# PCB-ACM.net
KiCad netlist of a schematic drawn in EAGLE
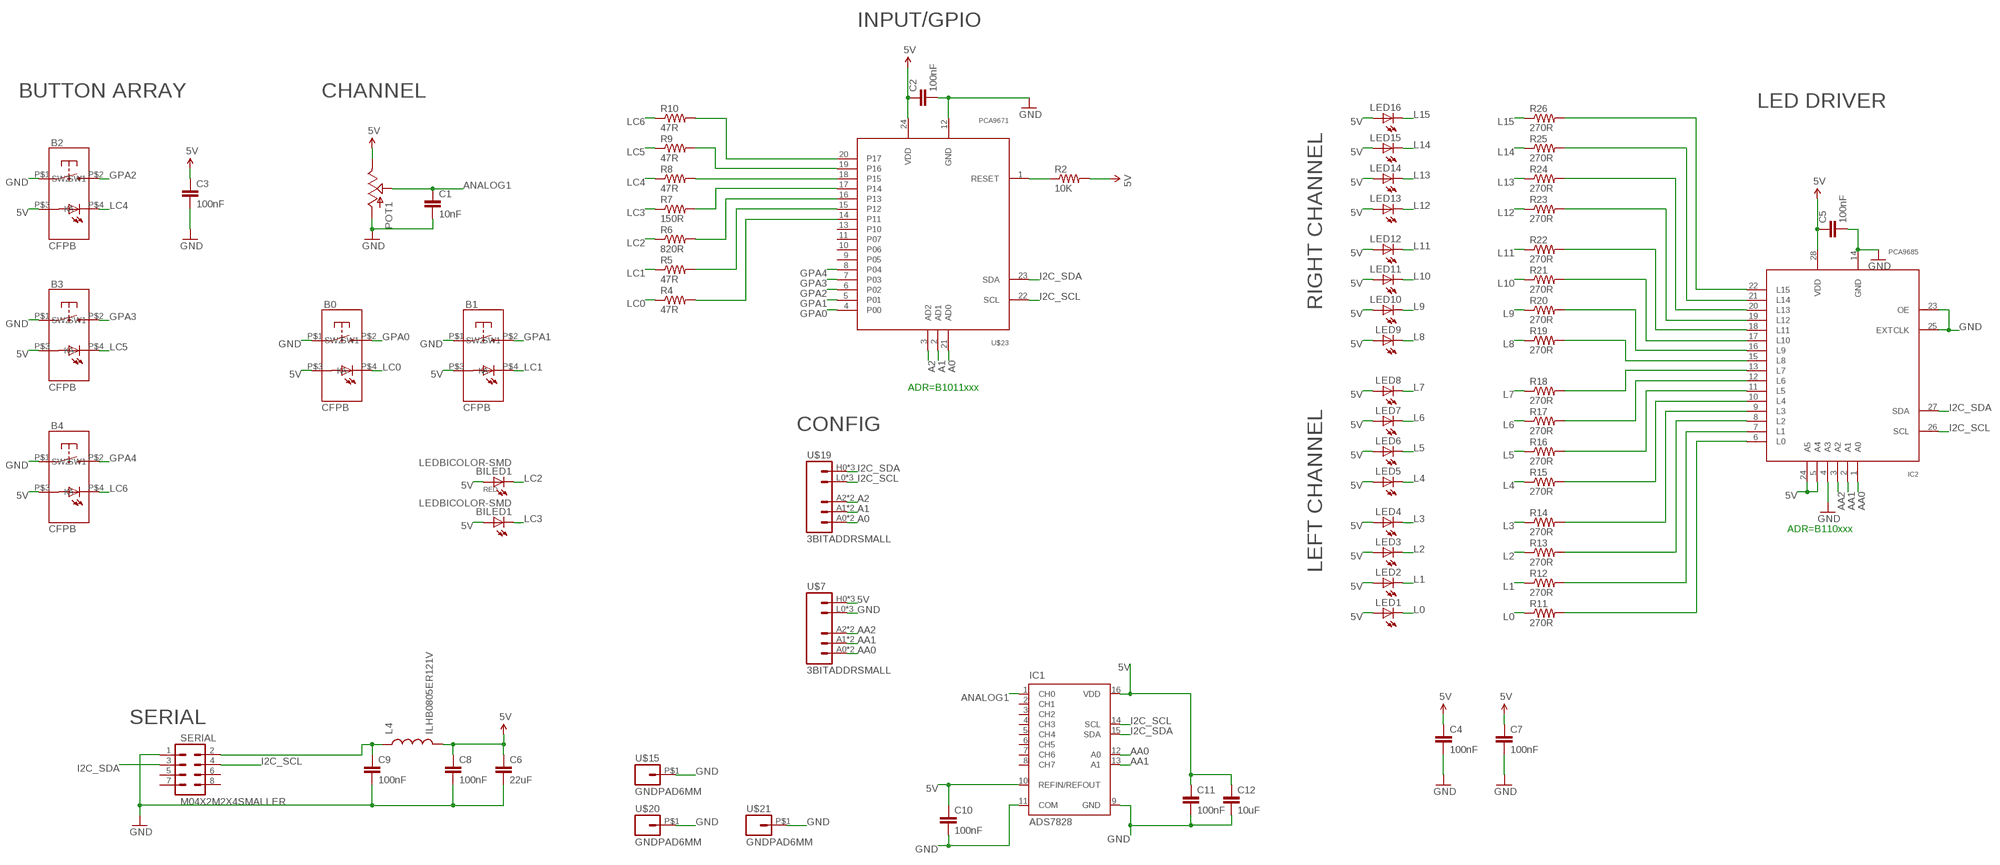
[diagram p0: schematic, sheet 1]

(export (version "E")
  (design (tool "Eeschema 10.0.6"))
  (components
    (comp (ref "B0")
      (value "CFPB")
      (footprint "eagle-import:CFPB-6_9MM")
      (libsource (lib "eagle-import") (part "CFPB"))
    )
    (comp (ref "B1")
      (value "CFPB")
      (footprint "eagle-import:CFPB-6_9MM")
      (libsource (lib "eagle-import") (part "CFPB"))
    )
    (comp (ref "B2")
      (value "CFPB")
      (footprint "eagle-import:CFPB-6_9MM")
      (libsource (lib "eagle-import") (part "CFPB"))
    )
    (comp (ref "B3")
      (value "CFPB")
      (footprint "eagle-import:CFPB-6_9MM")
      (libsource (lib "eagle-import") (part "CFPB"))
    )
    (comp (ref "B4")
      (value "CFPB")
      (footprint "eagle-import:CFPB-6_9MM")
      (libsource (lib "eagle-import") (part "CFPB"))
    )
    (comp (ref "BILED1")
      (value "LEDBICOLOR-SMD")
      (footprint "eagle-import:LEDBICOLOR-SMD")
      (libsource (lib "eagle-import") (part "LEDBICOLOR-SMD"))
    )
    (comp (ref "C1")
      (value "10nF")
      (footprint "eagle-import:0603-CAP")
      (libsource (lib "eagle-import") (part "CAP0603-CAP"))
    )
    (comp (ref "C2")
      (value "100nF")
      (footprint "eagle-import:0603-CAP")
      (libsource (lib "eagle-import") (part "CAP0603-CAP"))
    )
    (comp (ref "C3")
      (value "100nF")
      (footprint "eagle-import:0603-CAP")
      (libsource (lib "eagle-import") (part "CAP0603-CAP"))
    )
    (comp (ref "C4")
      (value "100nF")
      (footprint "eagle-import:0603-CAP")
      (libsource (lib "eagle-import") (part "CAP0603-CAP"))
    )
    (comp (ref "C5")
      (value "100nF")
      (footprint "eagle-import:0603-CAP")
      (libsource (lib "eagle-import") (part "CAP0603-CAP"))
    )
    (comp (ref "C6")
      (value "22uF")
      (footprint "eagle-import:0805")
      (libsource (lib "eagle-import") (part "CAP0805"))
    )
    (comp (ref "C7")
      (value "100nF")
      (footprint "eagle-import:0603-CAP")
      (libsource (lib "eagle-import") (part "CAP0603-CAP"))
    )
    (comp (ref "C8")
      (value "100nF")
      (footprint "eagle-import:0603-CAP")
      (libsource (lib "eagle-import") (part "CAP0603-CAP"))
    )
    (comp (ref "C9")
      (value "100nF")
      (footprint "eagle-import:0603-CAP")
      (libsource (lib "eagle-import") (part "CAP0603-CAP"))
    )
    (comp (ref "C10")
      (value "100nF")
      (footprint "eagle-import:0603-CAP")
      (libsource (lib "eagle-import") (part "CAP0603-CAP"))
    )
    (comp (ref "C11")
      (value "100nF")
      (footprint "eagle-import:0603-CAP")
      (libsource (lib "eagle-import") (part "CAP0603-CAP"))
    )
    (comp (ref "C12")
      (value "10uF")
      (footprint "eagle-import:0805")
      (libsource (lib "eagle-import") (part "CAP0805"))
    )
    (comp (ref "IC1")
      (value "ADS7828")
      (footprint "eagle-import:TSSOP16-PW")
      (fields (field (name "MF") "TEXAS INSTRUMENTS") (field (name "MPN") "ADS7828E/250"))
      (libsource (lib "eagle-import") (part "ADS7828"))
    )
    (comp (ref "IC2")
      (value "PCA9685")
      (footprint "eagle-import:TSSOP28")
      (libsource (lib "eagle-import") (part "PCA9685"))
    )
    (comp (ref "L4")
      (value "ILHB0805ER121V")
      (footprint "eagle-import:0805")
      (libsource (lib "eagle-import") (part "INDUCTOR0805"))
    )
    (comp (ref "LED1")
      (value "LED3MM")
      (footprint "eagle-import:LED3MM")
      (libsource (lib "eagle-import") (part "LED3MM"))
    )
    (comp (ref "LED2")
      (value "LED3MM")
      (footprint "eagle-import:LED3MM")
      (libsource (lib "eagle-import") (part "LED3MM"))
    )
    (comp (ref "LED3")
      (value "LED3MM")
      (footprint "eagle-import:LED3MM")
      (libsource (lib "eagle-import") (part "LED3MM"))
    )
    (comp (ref "LED4")
      (value "LED3MM")
      (footprint "eagle-import:LED3MM")
      (libsource (lib "eagle-import") (part "LED3MM"))
    )
    (comp (ref "LED5")
      (value "LED3MM")
      (footprint "eagle-import:LED3MM")
      (libsource (lib "eagle-import") (part "LED3MM"))
    )
    (comp (ref "LED6")
      (value "LED3MM")
      (footprint "eagle-import:LED3MM")
      (libsource (lib "eagle-import") (part "LED3MM"))
    )
    (comp (ref "LED7")
      (value "LED3MM")
      (footprint "eagle-import:LED3MM")
      (libsource (lib "eagle-import") (part "LED3MM"))
    )
    (comp (ref "LED8")
      (value "LED3MM")
      (footprint "eagle-import:LED3MM")
      (libsource (lib "eagle-import") (part "LED3MM"))
    )
    (comp (ref "LED9")
      (value "LED3MM")
      (footprint "eagle-import:LED3MM")
      (libsource (lib "eagle-import") (part "LED3MM"))
    )
    (comp (ref "LED10")
      (value "LED3MM")
      (footprint "eagle-import:LED3MM")
      (libsource (lib "eagle-import") (part "LED3MM"))
    )
    (comp (ref "LED11")
      (value "LED3MM")
      (footprint "eagle-import:LED3MM")
      (libsource (lib "eagle-import") (part "LED3MM"))
    )
    (comp (ref "LED12")
      (value "LED3MM")
      (footprint "eagle-import:LED3MM")
      (libsource (lib "eagle-import") (part "LED3MM"))
    )
    (comp (ref "LED13")
      (value "LED3MM")
      (footprint "eagle-import:LED3MM")
      (libsource (lib "eagle-import") (part "LED3MM"))
    )
    (comp (ref "LED14")
      (value "LED3MM")
      (footprint "eagle-import:LED3MM")
      (libsource (lib "eagle-import") (part "LED3MM"))
    )
    (comp (ref "LED15")
      (value "LED3MM")
      (footprint "eagle-import:LED3MM")
      (libsource (lib "eagle-import") (part "LED3MM"))
    )
    (comp (ref "LED16")
      (value "LED3MM")
      (footprint "eagle-import:LED3MM")
      (libsource (lib "eagle-import") (part "LED3MM"))
    )
    (comp (ref "POT1")
      (value "POT")
      (footprint "eagle-import:ALPS_POT")
      (libsource (lib "eagle-import") (part "POT"))
    )
    (comp (ref "R2")
      (value "10K")
      (footprint "eagle-import:0603-RES")
      (libsource (lib "eagle-import") (part "RESISTOR0603-RES"))
    )
    (comp (ref "R4")
      (value "47R")
      (footprint "eagle-import:0603-RES")
      (libsource (lib "eagle-import") (part "RESISTOR0603-RES"))
    )
    (comp (ref "R5")
      (value "47R")
      (footprint "eagle-import:0603-RES")
      (libsource (lib "eagle-import") (part "RESISTOR0603-RES"))
    )
    (comp (ref "R6")
      (value "820R")
      (footprint "eagle-import:0603-RES")
      (libsource (lib "eagle-import") (part "RESISTOR0603-RES"))
    )
    (comp (ref "R7")
      (value "150R")
      (footprint "eagle-import:0603-RES")
      (libsource (lib "eagle-import") (part "RESISTOR0603-RES"))
    )
    (comp (ref "R8")
      (value "47R")
      (footprint "eagle-import:0603-RES")
      (libsource (lib "eagle-import") (part "RESISTOR0603-RES"))
    )
    (comp (ref "R9")
      (value "47R")
      (footprint "eagle-import:0603-RES")
      (libsource (lib "eagle-import") (part "RESISTOR0603-RES"))
    )
    (comp (ref "R10")
      (value "47R")
      (footprint "eagle-import:0603-RES")
      (libsource (lib "eagle-import") (part "RESISTOR0603-RES"))
    )
    (comp (ref "R11")
      (value "270R")
      (footprint "eagle-import:0603-RES")
      (libsource (lib "eagle-import") (part "RESISTOR0603-RES"))
    )
    (comp (ref "R12")
      (value "270R")
      (footprint "eagle-import:0603-RES")
      (libsource (lib "eagle-import") (part "RESISTOR0603-RES"))
    )
    (comp (ref "R13")
      (value "270R")
      (footprint "eagle-import:0603-RES")
      (libsource (lib "eagle-import") (part "RESISTOR0603-RES"))
    )
    (comp (ref "R14")
      (value "270R")
      (footprint "eagle-import:0603-RES")
      (libsource (lib "eagle-import") (part "RESISTOR0603-RES"))
    )
    (comp (ref "R15")
      (value "270R")
      (footprint "eagle-import:0603-RES")
      (libsource (lib "eagle-import") (part "RESISTOR0603-RES"))
    )
    (comp (ref "R16")
      (value "270R")
      (footprint "eagle-import:0603-RES")
      (libsource (lib "eagle-import") (part "RESISTOR0603-RES"))
    )
    (comp (ref "R17")
      (value "270R")
      (footprint "eagle-import:0603-RES")
      (libsource (lib "eagle-import") (part "RESISTOR0603-RES"))
    )
    (comp (ref "R18")
      (value "270R")
      (footprint "eagle-import:0603-RES")
      (libsource (lib "eagle-import") (part "RESISTOR0603-RES"))
    )
    (comp (ref "R19")
      (value "270R")
      (footprint "eagle-import:0603-RES")
      (libsource (lib "eagle-import") (part "RESISTOR0603-RES"))
    )
    (comp (ref "R20")
      (value "270R")
      (footprint "eagle-import:0603-RES")
      (libsource (lib "eagle-import") (part "RESISTOR0603-RES"))
    )
    (comp (ref "R21")
      (value "270R")
      (footprint "eagle-import:0603-RES")
      (libsource (lib "eagle-import") (part "RESISTOR0603-RES"))
    )
    (comp (ref "R22")
      (value "270R")
      (footprint "eagle-import:0603-RES")
      (libsource (lib "eagle-import") (part "RESISTOR0603-RES"))
    )
    (comp (ref "R23")
      (value "270R")
      (footprint "eagle-import:0603-RES")
      (libsource (lib "eagle-import") (part "RESISTOR0603-RES"))
    )
    (comp (ref "R24")
      (value "270R")
      (footprint "eagle-import:0603-RES")
      (libsource (lib "eagle-import") (part "RESISTOR0603-RES"))
    )
    (comp (ref "R25")
      (value "270R")
      (footprint "eagle-import:0603-RES")
      (libsource (lib "eagle-import") (part "RESISTOR0603-RES"))
    )
    (comp (ref "R26")
      (value "270R")
      (footprint "eagle-import:0603-RES")
      (libsource (lib "eagle-import") (part "RESISTOR0603-RES"))
    )
    (comp (ref "SERIAL")
      (value "M04X2M2X4SMALLER")
      (footprint "eagle-import:M2X4SMALLER")
      (libsource (lib "eagle-import") (part "M04X2M2X4SMALLER"))
    )
    (comp (ref "U$7")
      (value "3BITADDRSMALL")
      (footprint "eagle-import:3BITADDR_SMALL")
      (libsource (lib "eagle-import") (part "3BITADDRSMALL"))
    )
    (comp (ref "U$15")
      (value "GNDPAD6MM")
      (footprint "eagle-import:3.2MMPAD6MM")
      (libsource (lib "eagle-import") (part "GNDPAD6MM"))
    )
    (comp (ref "U$19")
      (value "3BITADDRSMALL")
      (footprint "eagle-import:3BITADDR_SMALL")
      (libsource (lib "eagle-import") (part "3BITADDRSMALL"))
    )
    (comp (ref "U$20")
      (value "GNDPAD6MM")
      (footprint "eagle-import:3.2MMPAD6MM")
      (libsource (lib "eagle-import") (part "GNDPAD6MM"))
    )
    (comp (ref "U$21")
      (value "GNDPAD6MM")
      (footprint "eagle-import:3.2MMPAD6MM")
      (libsource (lib "eagle-import") (part "GNDPAD6MM"))
    )
    (comp (ref "U$23")
      (value "PCA9671")
      (footprint "eagle-import:TSSOP24")
      (libsource (lib "eagle-import") (part "PCA9671"))
    )
  )
  (nets
    (net (code "1") (name "/A0") (class "Default")
      (node (ref "U$19") (pin "A0") (pinfunction "A0_A0") (pintype "passive"))
      (node (ref "U$19") (pin "AS0") (pinfunction "A0_AS0") (pintype "passive"))
      (node (ref "U$23") (pin "21") (pinfunction "AD0_21") (pintype "input"))
    )
    (net (code "2") (name "/A1") (class "Default")
      (node (ref "U$19") (pin "A1") (pinfunction "A1_A1") (pintype "passive"))
      (node (ref "U$19") (pin "AS1") (pinfunction "A1_AS1") (pintype "passive"))
      (node (ref "U$23") (pin "2") (pinfunction "AD1_2") (pintype "input"))
    )
    (net (code "3") (name "/A2") (class "Default")
      (node (ref "U$19") (pin "A2") (pinfunction "A2_A2") (pintype "passive"))
      (node (ref "U$19") (pin "AS2") (pinfunction "A2_AS2") (pintype "passive"))
      (node (ref "U$23") (pin "3") (pinfunction "AD2_3") (pintype "input"))
    )
    (net (code "4") (name "/AA0") (class "Default")
      (node (ref "IC1") (pin "12") (pinfunction "A0_12") (pintype "input"))
      (node (ref "IC2") (pin "1") (pinfunction "A0_1") (pintype "input"))
      (node (ref "U$7") (pin "A0") (pinfunction "A0_A0") (pintype "passive"))
      (node (ref "U$7") (pin "AS0") (pinfunction "A0_AS0") (pintype "passive"))
    )
    (net (code "5") (name "/AA1") (class "Default")
      (node (ref "IC1") (pin "13") (pinfunction "A1_13") (pintype "input"))
      (node (ref "IC2") (pin "2") (pinfunction "A1_2") (pintype "input"))
      (node (ref "U$7") (pin "A1") (pinfunction "A1_A1") (pintype "passive"))
      (node (ref "U$7") (pin "AS1") (pinfunction "A1_AS1") (pintype "passive"))
    )
    (net (code "6") (name "/AA2") (class "Default")
      (node (ref "IC2") (pin "3") (pinfunction "A2_3") (pintype "input"))
      (node (ref "U$7") (pin "A2") (pinfunction "A2_A2") (pintype "passive"))
      (node (ref "U$7") (pin "AS2") (pinfunction "A2_AS2") (pintype "passive"))
    )
    (net (code "7") (name "/ANALOG1") (class "Default")
      (node (ref "C1") (pin "1") (pinfunction "1_1") (pintype "passive"))
      (node (ref "IC1") (pin "1") (pinfunction "CH0_1") (pintype "input"))
      (node (ref "POT1") (pin "P$2") (pinfunction "S_P$2") (pintype "passive"))
    )
    (net (code "8") (name "/GPA0") (class "Default")
      (node (ref "B0") (pin "P$2") (pinfunction "SW2_P$2") (pintype "bidirectional"))
      (node (ref "U$23") (pin "4") (pinfunction "P00_4") (pintype "output"))
    )
    (net (code "9") (name "/GPA1") (class "Default")
      (node (ref "B1") (pin "P$2") (pinfunction "SW2_P$2") (pintype "bidirectional"))
      (node (ref "U$23") (pin "5") (pinfunction "P01_5") (pintype "output"))
    )
    (net (code "10") (name "/GPA2") (class "Default")
      (node (ref "B2") (pin "P$2") (pinfunction "SW2_P$2") (pintype "bidirectional"))
      (node (ref "U$23") (pin "6") (pinfunction "P02_6") (pintype "output"))
    )
    (net (code "11") (name "/GPA3") (class "Default")
      (node (ref "B3") (pin "P$2") (pinfunction "SW2_P$2") (pintype "bidirectional"))
      (node (ref "U$23") (pin "7") (pinfunction "P03_7") (pintype "output"))
    )
    (net (code "12") (name "/GPA4") (class "Default")
      (node (ref "B4") (pin "P$2") (pinfunction "SW2_P$2") (pintype "bidirectional"))
      (node (ref "U$23") (pin "8") (pinfunction "P04_8") (pintype "output"))
    )
    (net (code "13") (name "/I2C_SCL") (class "Default")
      (node (ref "IC1") (pin "14") (pinfunction "SCL_14") (pintype "input"))
      (node (ref "IC2") (pin "26") (pinfunction "SCL_26") (pintype "input"))
      (node (ref "SERIAL") (pin "4") (pinfunction "4_4") (pintype "passive"))
      (node (ref "U$19") (pin "L0") (pinfunction "GND_L0") (pintype "passive"))
      (node (ref "U$19") (pin "L1") (pinfunction "GND_L1") (pintype "passive"))
      (node (ref "U$19") (pin "L2") (pinfunction "GND_L2") (pintype "passive"))
      (node (ref "U$23") (pin "22") (pinfunction "SCL_22") (pintype "input"))
    )
    (net (code "14") (name "/I2C_SDA") (class "Default")
      (node (ref "IC1") (pin "15") (pinfunction "SDA_15") (pintype "bidirectional"))
      (node (ref "IC2") (pin "27") (pinfunction "SDA_27") (pintype "input"))
      (node (ref "SERIAL") (pin "3") (pinfunction "3_3") (pintype "passive"))
      (node (ref "U$19") (pin "H0") (pinfunction "VCC_H0") (pintype "passive"))
      (node (ref "U$19") (pin "H1") (pinfunction "VCC_H1") (pintype "passive"))
      (node (ref "U$19") (pin "H2") (pinfunction "VCC_H2") (pintype "passive"))
      (node (ref "U$23") (pin "23") (pinfunction "SDA_23") (pintype "input"))
    )
    (net (code "15") (name "/L0") (class "Default")
      (node (ref "LED1") (pin "K") (pinfunction "C_K") (pintype "passive"))
      (node (ref "R11") (pin "1") (pinfunction "1_1") (pintype "passive"))
    )
    (net (code "16") (name "/L1") (class "Default")
      (node (ref "LED2") (pin "K") (pinfunction "C_K") (pintype "passive"))
      (node (ref "R12") (pin "1") (pinfunction "1_1") (pintype "passive"))
    )
    (net (code "17") (name "/L2") (class "Default")
      (node (ref "LED3") (pin "K") (pinfunction "C_K") (pintype "passive"))
      (node (ref "R13") (pin "1") (pinfunction "1_1") (pintype "passive"))
    )
    (net (code "18") (name "/L3") (class "Default")
      (node (ref "LED4") (pin "K") (pinfunction "C_K") (pintype "passive"))
      (node (ref "R14") (pin "1") (pinfunction "1_1") (pintype "passive"))
    )
    (net (code "19") (name "/L4") (class "Default")
      (node (ref "LED5") (pin "K") (pinfunction "C_K") (pintype "passive"))
      (node (ref "R15") (pin "1") (pinfunction "1_1") (pintype "passive"))
    )
    (net (code "20") (name "/L5") (class "Default")
      (node (ref "LED6") (pin "K") (pinfunction "C_K") (pintype "passive"))
      (node (ref "R16") (pin "1") (pinfunction "1_1") (pintype "passive"))
    )
    (net (code "21") (name "/L6") (class "Default")
      (node (ref "LED7") (pin "K") (pinfunction "C_K") (pintype "passive"))
      (node (ref "R17") (pin "1") (pinfunction "1_1") (pintype "passive"))
    )
    (net (code "22") (name "/L7") (class "Default")
      (node (ref "LED8") (pin "K") (pinfunction "C_K") (pintype "passive"))
      (node (ref "R18") (pin "1") (pinfunction "1_1") (pintype "passive"))
    )
    (net (code "23") (name "/L8") (class "Default")
      (node (ref "LED9") (pin "K") (pinfunction "C_K") (pintype "passive"))
      (node (ref "R19") (pin "1") (pinfunction "1_1") (pintype "passive"))
    )
    (net (code "24") (name "/L9") (class "Default")
      (node (ref "LED10") (pin "K") (pinfunction "C_K") (pintype "passive"))
      (node (ref "R20") (pin "1") (pinfunction "1_1") (pintype "passive"))
    )
    (net (code "25") (name "/L10") (class "Default")
      (node (ref "LED11") (pin "K") (pinfunction "C_K") (pintype "passive"))
      (node (ref "R21") (pin "1") (pinfunction "1_1") (pintype "passive"))
    )
    (net (code "26") (name "/L11") (class "Default")
      (node (ref "LED12") (pin "K") (pinfunction "C_K") (pintype "passive"))
      (node (ref "R22") (pin "1") (pinfunction "1_1") (pintype "passive"))
    )
    (net (code "27") (name "/L12") (class "Default")
      (node (ref "LED13") (pin "K") (pinfunction "C_K") (pintype "passive"))
      (node (ref "R23") (pin "1") (pinfunction "1_1") (pintype "passive"))
    )
    (net (code "28") (name "/L13") (class "Default")
      (node (ref "LED14") (pin "K") (pinfunction "C_K") (pintype "passive"))
      (node (ref "R24") (pin "1") (pinfunction "1_1") (pintype "passive"))
    )
    (net (code "29") (name "/L14") (class "Default")
      (node (ref "LED15") (pin "K") (pinfunction "C_K") (pintype "passive"))
      (node (ref "R25") (pin "1") (pinfunction "1_1") (pintype "passive"))
    )
    (net (code "30") (name "/L15") (class "Default")
      (node (ref "LED16") (pin "K") (pinfunction "C_K") (pintype "passive"))
      (node (ref "R26") (pin "1") (pinfunction "1_1") (pintype "passive"))
    )
    (net (code "31") (name "/LC0") (class "Default")
      (node (ref "B0") (pin "P$4") (pinfunction "K_P$4") (pintype "bidirectional"))
      (node (ref "R4") (pin "1") (pinfunction "1_1") (pintype "passive"))
    )
    (net (code "32") (name "/LC1") (class "Default")
      (node (ref "B1") (pin "P$4") (pinfunction "K_P$4") (pintype "bidirectional"))
      (node (ref "R5") (pin "1") (pinfunction "1_1") (pintype "passive"))
    )
    (net (code "33") (name "/LC2") (class "Default")
      (node (ref "BILED1") (pin "P$2") (pinfunction "C_P$2") (pintype "passive"))
      (node (ref "R6") (pin "1") (pinfunction "1_1") (pintype "passive"))
    )
    (net (code "34") (name "/LC3") (class "Default")
      (node (ref "BILED1") (pin "P$4") (pinfunction "C1_P$4") (pintype "passive"))
      (node (ref "R7") (pin "1") (pinfunction "1_1") (pintype "passive"))
    )
    (net (code "35") (name "/LC4") (class "Default")
      (node (ref "B2") (pin "P$4") (pinfunction "K_P$4") (pintype "bidirectional"))
      (node (ref "R8") (pin "1") (pinfunction "1_1") (pintype "passive"))
    )
    (net (code "36") (name "/LC5") (class "Default")
      (node (ref "B3") (pin "P$4") (pinfunction "K_P$4") (pintype "bidirectional"))
      (node (ref "R9") (pin "1") (pinfunction "1_1") (pintype "passive"))
    )
    (net (code "37") (name "/LC6") (class "Default")
      (node (ref "B4") (pin "P$4") (pinfunction "K_P$4") (pintype "bidirectional"))
      (node (ref "R10") (pin "1") (pinfunction "1_1") (pintype "passive"))
    )
    (net (code "38") (name "5V") (class "Default")
      (node (ref "B0") (pin "P$3") (pinfunction "A_P$3") (pintype "bidirectional"))
      (node (ref "B1") (pin "P$3") (pinfunction "A_P$3") (pintype "bidirectional"))
      (node (ref "B2") (pin "P$3") (pinfunction "A_P$3") (pintype "bidirectional"))
      (node (ref "B3") (pin "P$3") (pinfunction "A_P$3") (pintype "bidirectional"))
      (node (ref "B4") (pin "P$3") (pinfunction "A_P$3") (pintype "bidirectional"))
      (node (ref "BILED1") (pin "P$1") (pinfunction "A_P$1") (pintype "passive"))
      (node (ref "BILED1") (pin "P$3") (pinfunction "A1_P$3") (pintype "passive"))
      (node (ref "C10") (pin "1") (pinfunction "1_1") (pintype "passive"))
      (node (ref "C11") (pin "1") (pinfunction "1_1") (pintype "passive"))
      (node (ref "C12") (pin "1") (pinfunction "1_1") (pintype "passive"))
      (node (ref "C2") (pin "1") (pinfunction "1_1") (pintype "passive"))
      (node (ref "C3") (pin "1") (pinfunction "1_1") (pintype "passive"))
      (node (ref "C4") (pin "1") (pinfunction "1_1") (pintype "passive"))
      (node (ref "C5") (pin "1") (pinfunction "1_1") (pintype "passive"))
      (node (ref "C6") (pin "1") (pinfunction "1_1") (pintype "passive"))
      (node (ref "C7") (pin "1") (pinfunction "1_1") (pintype "passive"))
      (node (ref "C8") (pin "1") (pinfunction "1_1") (pintype "passive"))
      (node (ref "IC1") (pin "10") (pinfunction "REFIN/REFOUT_10") (pintype "passive"))
      (node (ref "IC1") (pin "16") (pinfunction "VDD_16") (pintype "power_in"))
      (node (ref "IC2") (pin "24") (pinfunction "A5_24") (pintype "input"))
      (node (ref "IC2") (pin "28") (pinfunction "VDD_28") (pintype "power_in"))
      (node (ref "IC2") (pin "5") (pinfunction "A4_5") (pintype "input"))
      (node (ref "L4") (pin "2") (pinfunction "2_2") (pintype "passive"))
      (node (ref "LED1") (pin "A") (pinfunction "A_A") (pintype "passive"))
      (node (ref "LED10") (pin "A") (pinfunction "A_A") (pintype "passive"))
      (node (ref "LED11") (pin "A") (pinfunction "A_A") (pintype "passive"))
      (node (ref "LED12") (pin "A") (pinfunction "A_A") (pintype "passive"))
      (node (ref "LED13") (pin "A") (pinfunction "A_A") (pintype "passive"))
      (node (ref "LED14") (pin "A") (pinfunction "A_A") (pintype "passive"))
      (node (ref "LED15") (pin "A") (pinfunction "A_A") (pintype "passive"))
      (node (ref "LED16") (pin "A") (pinfunction "A_A") (pintype "passive"))
      (node (ref "LED2") (pin "A") (pinfunction "A_A") (pintype "passive"))
      (node (ref "LED3") (pin "A") (pinfunction "A_A") (pintype "passive"))
      (node (ref "LED4") (pin "A") (pinfunction "A_A") (pintype "passive"))
      (node (ref "LED5") (pin "A") (pinfunction "A_A") (pintype "passive"))
      (node (ref "LED6") (pin "A") (pinfunction "A_A") (pintype "passive"))
      (node (ref "LED7") (pin "A") (pinfunction "A_A") (pintype "passive"))
      (node (ref "LED8") (pin "A") (pinfunction "A_A") (pintype "passive"))
      (node (ref "LED9") (pin "A") (pinfunction "A_A") (pintype "passive"))
      (node (ref "POT1") (pin "P$1") (pinfunction "E_P$1") (pintype "passive"))
      (node (ref "R2") (pin "2") (pinfunction "2_2") (pintype "passive"))
      (node (ref "U$23") (pin "24") (pinfunction "VDD_24") (pintype "power_in"))
      (node (ref "U$7") (pin "H0") (pinfunction "VCC_H0") (pintype "passive"))
      (node (ref "U$7") (pin "H1") (pinfunction "VCC_H1") (pintype "passive"))
      (node (ref "U$7") (pin "H2") (pinfunction "VCC_H2") (pintype "passive"))
    )
    (net (code "39") (name "GND") (class "Default")
      (node (ref "B0") (pin "P$1") (pinfunction "SW1_P$1") (pintype "bidirectional"))
      (node (ref "B1") (pin "P$1") (pinfunction "SW1_P$1") (pintype "bidirectional"))
      (node (ref "B2") (pin "P$1") (pinfunction "SW1_P$1") (pintype "bidirectional"))
      (node (ref "B3") (pin "P$1") (pinfunction "SW1_P$1") (pintype "bidirectional"))
      (node (ref "B4") (pin "P$1") (pinfunction "SW1_P$1") (pintype "bidirectional"))
      (node (ref "C1") (pin "2") (pinfunction "2_2") (pintype "passive"))
      (node (ref "C10") (pin "2") (pinfunction "2_2") (pintype "passive"))
      (node (ref "C11") (pin "2") (pinfunction "2_2") (pintype "passive"))
      (node (ref "C12") (pin "2") (pinfunction "2_2") (pintype "passive"))
      (node (ref "C2") (pin "2") (pinfunction "2_2") (pintype "passive"))
      (node (ref "C3") (pin "2") (pinfunction "2_2") (pintype "passive"))
      (node (ref "C4") (pin "2") (pinfunction "2_2") (pintype "passive"))
      (node (ref "C5") (pin "2") (pinfunction "2_2") (pintype "passive"))
      (node (ref "C6") (pin "2") (pinfunction "2_2") (pintype "passive"))
      (node (ref "C7") (pin "2") (pinfunction "2_2") (pintype "passive"))
      (node (ref "C8") (pin "2") (pinfunction "2_2") (pintype "passive"))
      (node (ref "C9") (pin "2") (pinfunction "2_2") (pintype "passive"))
      (node (ref "IC1") (pin "11") (pinfunction "COM_11") (pintype "input"))
      (node (ref "IC1") (pin "9") (pinfunction "GND_9") (pintype "power_in"))
      (node (ref "IC2") (pin "14") (pinfunction "GND_14") (pintype "power_in"))
      (node (ref "IC2") (pin "23") (pinfunction "OE_23") (pintype "input"))
      (node (ref "IC2") (pin "25") (pinfunction "EXTCLK_25") (pintype "input"))
      (node (ref "IC2") (pin "4") (pinfunction "A3_4") (pintype "input"))
      (node (ref "POT1") (pin "P$3") (pinfunction "A_P$3") (pintype "passive"))
      (node (ref "SERIAL") (pin "1") (pinfunction "1_1") (pintype "passive"))
      (node (ref "U$15") (pin "P$1") (pinfunction "1_P$1") (pintype "passive"))
      (node (ref "U$20") (pin "P$1") (pinfunction "1_P$1") (pintype "passive"))
      (node (ref "U$21") (pin "P$1") (pinfunction "1_P$1") (pintype "passive"))
      (node (ref "U$23") (pin "12") (pinfunction "GND_12") (pintype "power_in"))
      (node (ref "U$7") (pin "L0") (pinfunction "GND_L0") (pintype "passive"))
      (node (ref "U$7") (pin "L1") (pinfunction "GND_L1") (pintype "passive"))
      (node (ref "U$7") (pin "L2") (pinfunction "GND_L2") (pintype "passive"))
    )
    (net (code "40") (name "Net-(C9-Pad1)") (class "Default")
      (node (ref "C9") (pin "1") (pinfunction "1_1") (pintype "passive"))
      (node (ref "L4") (pin "1") (pinfunction "1_1") (pintype "passive"))
      (node (ref "SERIAL") (pin "2") (pinfunction "2_2") (pintype "passive"))
    )
    (net (code "41") (name "Net-(IC2-L0)") (class "Default")
      (node (ref "IC2") (pin "6") (pinfunction "L0_6") (pintype "output"))
      (node (ref "R11") (pin "2") (pinfunction "2_2") (pintype "passive"))
    )
    (net (code "42") (name "Net-(IC2-L1)") (class "Default")
      (node (ref "IC2") (pin "7") (pinfunction "L1_7") (pintype "output"))
      (node (ref "R12") (pin "2") (pinfunction "2_2") (pintype "passive"))
    )
    (net (code "43") (name "Net-(IC2-L2)") (class "Default")
      (node (ref "IC2") (pin "8") (pinfunction "L2_8") (pintype "output"))
      (node (ref "R13") (pin "2") (pinfunction "2_2") (pintype "passive"))
    )
    (net (code "44") (name "Net-(IC2-L3)") (class "Default")
      (node (ref "IC2") (pin "9") (pinfunction "L3_9") (pintype "output"))
      (node (ref "R14") (pin "2") (pinfunction "2_2") (pintype "passive"))
    )
    (net (code "45") (name "Net-(IC2-L4)") (class "Default")
      (node (ref "IC2") (pin "10") (pinfunction "L4_10") (pintype "output"))
      (node (ref "R15") (pin "2") (pinfunction "2_2") (pintype "passive"))
    )
    (net (code "46") (name "Net-(IC2-L5)") (class "Default")
      (node (ref "IC2") (pin "11") (pinfunction "L5_11") (pintype "output"))
      (node (ref "R16") (pin "2") (pinfunction "2_2") (pintype "passive"))
    )
    (net (code "47") (name "Net-(IC2-L6)") (class "Default")
      (node (ref "IC2") (pin "12") (pinfunction "L6_12") (pintype "output"))
      (node (ref "R17") (pin "2") (pinfunction "2_2") (pintype "passive"))
    )
    (net (code "48") (name "Net-(IC2-L7)") (class "Default")
      (node (ref "IC2") (pin "13") (pinfunction "L7_13") (pintype "output"))
      (node (ref "R18") (pin "2") (pinfunction "2_2") (pintype "passive"))
    )
    (net (code "49") (name "Net-(IC2-L8)") (class "Default")
      (node (ref "IC2") (pin "15") (pinfunction "L8_15") (pintype "output"))
      (node (ref "R19") (pin "2") (pinfunction "2_2") (pintype "passive"))
    )
    (net (code "50") (name "Net-(IC2-L9)") (class "Default")
      (node (ref "IC2") (pin "16") (pinfunction "L9_16") (pintype "output"))
      (node (ref "R20") (pin "2") (pinfunction "2_2") (pintype "passive"))
    )
    (net (code "51") (name "Net-(IC2-L10)") (class "Default")
      (node (ref "IC2") (pin "17") (pinfunction "L10_17") (pintype "output"))
      (node (ref "R21") (pin "2") (pinfunction "2_2") (pintype "passive"))
    )
    (net (code "52") (name "Net-(IC2-L11)") (class "Default")
      (node (ref "IC2") (pin "18") (pinfunction "L11_18") (pintype "output"))
      (node (ref "R22") (pin "2") (pinfunction "2_2") (pintype "passive"))
    )
    (net (code "53") (name "Net-(IC2-L12)") (class "Default")
      (node (ref "IC2") (pin "19") (pinfunction "L12_19") (pintype "output"))
      (node (ref "R23") (pin "2") (pinfunction "2_2") (pintype "passive"))
    )
    (net (code "54") (name "Net-(IC2-L13)") (class "Default")
      (node (ref "IC2") (pin "20") (pinfunction "L13_20") (pintype "output"))
      (node (ref "R24") (pin "2") (pinfunction "2_2") (pintype "passive"))
    )
    (net (code "55") (name "Net-(IC2-L14)") (class "Default")
      (node (ref "IC2") (pin "21") (pinfunction "L14_21") (pintype "output"))
      (node (ref "R25") (pin "2") (pinfunction "2_2") (pintype "passive"))
    )
    (net (code "56") (name "Net-(IC2-L15)") (class "Default")
      (node (ref "IC2") (pin "22") (pinfunction "L15_22") (pintype "output"))
      (node (ref "R26") (pin "2") (pinfunction "2_2") (pintype "passive"))
    )
    (net (code "57") (name "Net-(U$23-P11)") (class "Default")
      (node (ref "R4") (pin "2") (pinfunction "2_2") (pintype "passive"))
      (node (ref "U$23") (pin "14") (pinfunction "P11_14") (pintype "output"))
    )
    (net (code "58") (name "Net-(U$23-P12)") (class "Default")
      (node (ref "R5") (pin "2") (pinfunction "2_2") (pintype "passive"))
      (node (ref "U$23") (pin "15") (pinfunction "P12_15") (pintype "output"))
    )
    (net (code "59") (name "Net-(U$23-P13)") (class "Default")
      (node (ref "R6") (pin "2") (pinfunction "2_2") (pintype "passive"))
      (node (ref "U$23") (pin "16") (pinfunction "P13_16") (pintype "output"))
    )
    (net (code "60") (name "Net-(U$23-P14)") (class "Default")
      (node (ref "R7") (pin "2") (pinfunction "2_2") (pintype "passive"))
      (node (ref "U$23") (pin "17") (pinfunction "P14_17") (pintype "output"))
    )
    (net (code "61") (name "Net-(U$23-P15)") (class "Default")
      (node (ref "R8") (pin "2") (pinfunction "2_2") (pintype "passive"))
      (node (ref "U$23") (pin "18") (pinfunction "P15_18") (pintype "output"))
    )
    (net (code "62") (name "Net-(U$23-P16)") (class "Default")
      (node (ref "R9") (pin "2") (pinfunction "2_2") (pintype "passive"))
      (node (ref "U$23") (pin "19") (pinfunction "P16_19") (pintype "output"))
    )
    (net (code "63") (name "Net-(U$23-P17)") (class "Default")
      (node (ref "R10") (pin "2") (pinfunction "2_2") (pintype "passive"))
      (node (ref "U$23") (pin "20") (pinfunction "P17_20") (pintype "output"))
    )
    (net (code "64") (name "Net-(U$23-RESET)") (class "Default")
      (node (ref "R2") (pin "1") (pinfunction "1_1") (pintype "passive"))
      (node (ref "U$23") (pin "1") (pinfunction "RESET_1") (pintype "input"))
    )
    (net (code "65") (name "unconnected-(IC1-CH1-Pad2)") (class "Default")
      (node (ref "IC1") (pin "2") (pinfunction "CH1_2") (pintype "input"))
    )
    (net (code "66") (name "unconnected-(IC1-CH2-Pad3)") (class "Default")
      (node (ref "IC1") (pin "3") (pinfunction "CH2_3") (pintype "input"))
    )
    (net (code "67") (name "unconnected-(IC1-CH3-Pad4)") (class "Default")
      (node (ref "IC1") (pin "4") (pinfunction "CH3_4") (pintype "input"))
    )
    (net (code "68") (name "unconnected-(IC1-CH4-Pad5)") (class "Default")
      (node (ref "IC1") (pin "5") (pinfunction "CH4_5") (pintype "input"))
    )
    (net (code "69") (name "unconnected-(IC1-CH5-Pad6)") (class "Default")
      (node (ref "IC1") (pin "6") (pinfunction "CH5_6") (pintype "input"))
    )
    (net (code "70") (name "unconnected-(IC1-CH6-Pad7)") (class "Default")
      (node (ref "IC1") (pin "7") (pinfunction "CH6_7") (pintype "input"))
    )
    (net (code "71") (name "unconnected-(IC1-CH7-Pad8)") (class "Default")
      (node (ref "IC1") (pin "8") (pinfunction "CH7_8") (pintype "input"))
    )
    (net (code "72") (name "unconnected-(SERIAL-Pad5)") (class "Default")
      (node (ref "SERIAL") (pin "5") (pinfunction "5_5") (pintype "passive"))
    )
    (net (code "73") (name "unconnected-(SERIAL-Pad6)") (class "Default")
      (node (ref "SERIAL") (pin "6") (pinfunction "6_6") (pintype "passive"))
    )
    (net (code "74") (name "unconnected-(SERIAL-Pad7)") (class "Default")
      (node (ref "SERIAL") (pin "7") (pinfunction "7_7") (pintype "passive"))
    )
    (net (code "75") (name "unconnected-(SERIAL-Pad8)") (class "Default")
      (node (ref "SERIAL") (pin "8") (pinfunction "8_8") (pintype "passive"))
    )
    (net (code "76") (name "unconnected-(U$23-P05-Pad9)") (class "Default")
      (node (ref "U$23") (pin "9") (pinfunction "P05_9") (pintype "output"))
    )
    (net (code "77") (name "unconnected-(U$23-P06-Pad10)") (class "Default")
      (node (ref "U$23") (pin "10") (pinfunction "P06_10") (pintype "output"))
    )
    (net (code "78") (name "unconnected-(U$23-P07-Pad11)") (class "Default")
      (node (ref "U$23") (pin "11") (pinfunction "P07_11") (pintype "output"))
    )
    (net (code "79") (name "unconnected-(U$23-P10-Pad13)") (class "Default")
      (node (ref "U$23") (pin "13") (pinfunction "P10_13") (pintype "output"))
    )
  )
)
